# ARC.net
KiCad netlist of a schematic drawn in Altium Designer
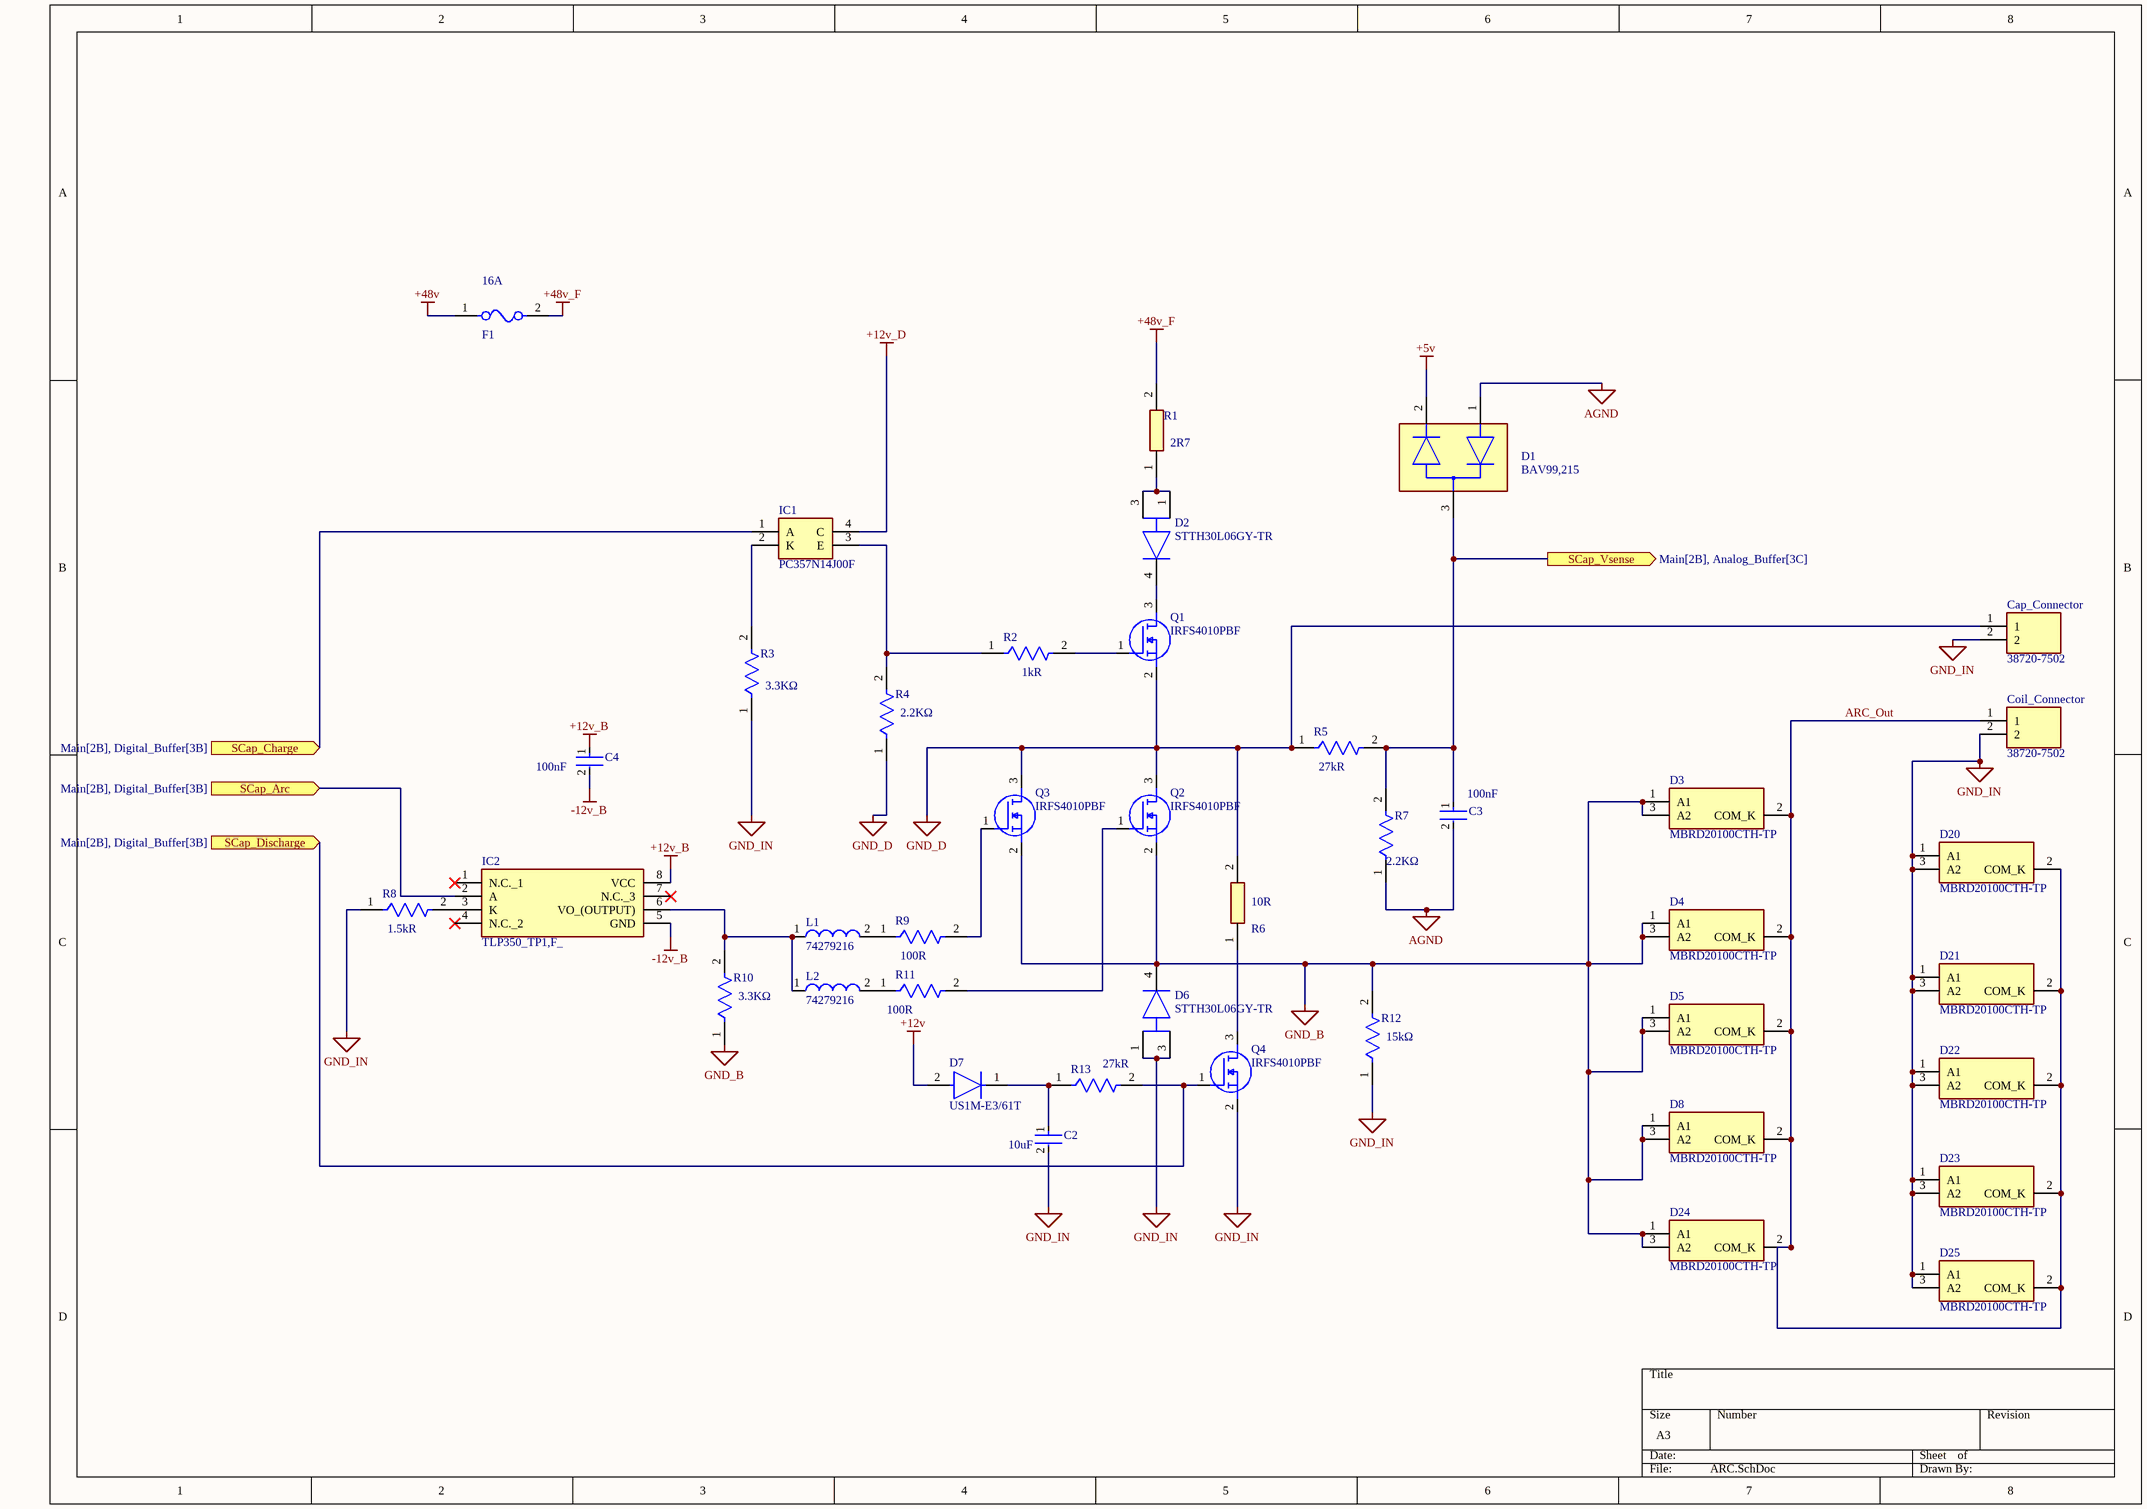
[diagram p0: ARC.SchDoc]

(export (version "E")
  (design (tool "Eeschema 10.0.6"))
  (components
    (comp (ref "C2")
      (value "GRM31CR71E106KA12L")
      (footprint "FP-GRM31C-0_2-e0_3_0_8-MFG")
      (description "Chip Multilayer Ceramic Capacitors for General Purpose, 1206, 10uF, X7R, 15%, 10%, 25V")
      (fields
        (field (name "TOLERANCE") "10%")
        (field (name "VOLTAGE") "25V")
        (field (name "CAPACITANCE") "10uF")
      )
      (libsource (lib "Altium Content Vault") (part "02cd4be3c70576c341d710602a673aa"))
    )
    (comp (ref "C3")
      (value "12065C104KAT2A")
      (footprint "FP-1206-L_3_2_0_2-W_1_6_0-MFG")
      (description "General Purpose Ceramic Capacitor, 1206, 100nF, 10%, X7R, 15%, 50V")
      (fields
        (field (name "TOLERANCE") "10%")
        (field (name "VOLTAGE") "50V")
        (field (name "CAPACITANCE") "100nF")
      )
      (libsource (lib "Altium Content Vault") (part "02cd4be3c70576c341d710602a673aa"))
    )
    (comp (ref "C4")
      (value "12065C104KAT2A")
      (footprint "FP-1206-L_3_2_0_2-W_1_6_0-MFG")
      (description "General Purpose Ceramic Capacitor, 1206, 100nF, 10%, X7R, 15%, 50V")
      (fields
        (field (name "TOLERANCE") "10%")
        (field (name "VOLTAGE") "50V")
        (field (name "CAPACITANCE") "100nF")
      )
      (libsource (lib "Altium Content Vault") (part "02cd4be3c70576c341d710602a673aa"))
    )
    (comp (ref "Cap_Connector")
      (value "38720-7502")
      (footprint "SamacSys:387207502")
      (description "Connector")
      (fields (field (name "MOUSER PART NUMBER") "538-38720-7502"))
      (libsource (lib "*") (part "38720-7502"))
    )
    (comp (ref "Coil_Connector")
      (value "38720-7502")
      (footprint "SamacSys:387207502")
      (description "Connector")
      (fields (field (name "MOUSER PART NUMBER") "538-38720-7502"))
      (libsource (lib "*") (part "38720-7502"))
    )
    (comp (ref "D1")
      (value "BAV99,215")
      (footprint "FP-SOT23-MFG")
      (description "DIODE ARRAY GP 100V 215MA SOT23")
      (libsource (lib "Altium Content Vault") (part "86a7eb6839269cc1691df5cbdd99f75"))
    )
    (comp (ref "D2")
      (value "STTH30L06GY-TR")
      (footprint "FP-D2PAK-MFG")
      (description "DIODE GEN PURP 600V 30A D2PAK")
      (fields
        (field (name "OCTOPART") "https://octopart.com/stth30l06gy-tr-stmicroelectronics-26451410")
        (field (name "MANUFACTURER") "STMicroelectronics")
      )
      (libsource (lib "Altium Content Vault") (part "255d24a1d5026c405cb8a6d03432c93"))
    )
    (comp (ref "D3")
      (value "MBRD20100CTH-TP")
      (footprint "SamacSys:MBRD20100CTHTP")
      (description "Schottky Diode")
      (fields (field (name "MOUSER PART NUMBER") "833-MBRD20100CTH-TP"))
      (libsource (lib "*") (part "MBRD20100CTH-TP"))
    )
    (comp (ref "D4")
      (value "MBRD20100CTH-TP")
      (footprint "SamacSys:MBRD20100CTHTP")
      (description "Schottky Diode")
      (fields (field (name "MOUSER PART NUMBER") "833-MBRD20100CTH-TP"))
      (libsource (lib "*") (part "MBRD20100CTH-TP"))
    )
    (comp (ref "D5")
      (value "MBRD20100CTH-TP")
      (footprint "SamacSys:MBRD20100CTHTP")
      (description "Schottky Diode")
      (fields (field (name "MOUSER PART NUMBER") "833-MBRD20100CTH-TP"))
      (libsource (lib "*") (part "MBRD20100CTH-TP"))
    )
    (comp (ref "D6")
      (value "STTH30L06GY-TR")
      (footprint "FP-D2PAK-MFG")
      (description "DIODE GEN PURP 600V 30A D2PAK")
      (fields
        (field (name "OCTOPART") "https://octopart.com/stth30l06gy-tr-stmicroelectronics-26451410")
        (field (name "MANUFACTURER") "STMicroelectronics")
      )
      (libsource (lib "Altium Content Vault") (part "255d24a1d5026c405cb8a6d03432c93"))
    )
    (comp (ref "D7")
      (value "US1M-E3/61T")
      (footprint "FP-95400-MFG")
      (description "DIODE GEN PURP 1KV 1A DO214AC")
      (fields
        (field (name "OCTOPART") "https://octopart.com/us1m-e3%2F61t-vishay-39553152")
        (field (name "MANUFACTURER") "Vishay")
      )
      (libsource (lib "Altium Content Vault") (part "d7152d700b627762746794eb795d46e"))
    )
    (comp (ref "D8")
      (value "MBRD20100CTH-TP")
      (footprint "SamacSys:MBRD20100CTHTP")
      (description "Schottky Diode")
      (fields (field (name "MOUSER PART NUMBER") "833-MBRD20100CTH-TP"))
      (libsource (lib "*") (part "MBRD20100CTH-TP"))
    )
    (comp (ref "D20")
      (value "MBRD20100CTH-TP")
      (footprint "SamacSys:MBRD20100CTHTP")
      (description "Schottky Diode")
      (fields (field (name "MOUSER PART NUMBER") "833-MBRD20100CTH-TP"))
      (libsource (lib "*") (part "MBRD20100CTH-TP"))
    )
    (comp (ref "D21")
      (value "MBRD20100CTH-TP")
      (footprint "SamacSys:MBRD20100CTHTP")
      (description "Schottky Diode")
      (fields (field (name "MOUSER PART NUMBER") "833-MBRD20100CTH-TP"))
      (libsource (lib "*") (part "MBRD20100CTH-TP"))
    )
    (comp (ref "D22")
      (value "MBRD20100CTH-TP")
      (footprint "SamacSys:MBRD20100CTHTP")
      (description "Schottky Diode")
      (fields (field (name "MOUSER PART NUMBER") "833-MBRD20100CTH-TP"))
      (libsource (lib "*") (part "MBRD20100CTH-TP"))
    )
    (comp (ref "D23")
      (value "MBRD20100CTH-TP")
      (footprint "SamacSys:MBRD20100CTHTP")
      (description "Schottky Diode")
      (fields (field (name "MOUSER PART NUMBER") "833-MBRD20100CTH-TP"))
      (libsource (lib "*") (part "MBRD20100CTH-TP"))
    )
    (comp (ref "D24")
      (value "MBRD20100CTH-TP")
      (footprint "SamacSys:MBRD20100CTHTP")
      (description "Schottky Diode")
      (fields (field (name "MOUSER PART NUMBER") "833-MBRD20100CTH-TP"))
      (libsource (lib "*") (part "MBRD20100CTH-TP"))
    )
    (comp (ref "D25")
      (value "MBRD20100CTH-TP")
      (footprint "SamacSys:MBRD20100CTHTP")
      (description "Schottky Diode")
      (fields (field (name "MOUSER PART NUMBER") "833-MBRD20100CTH-TP"))
      (libsource (lib "*") (part "MBRD20100CTH-TP"))
    )
    (comp (ref "F1")
      (value "0031.8231")
      (footprint "FP-0031_8231-MFG")
      (description "FUSE BLOK CARTRIDGE 600V 16A PCB")
      (fields
        (field (name "OCTOPART") "https://octopart.com/0031.8231-schurter-8659")
        (field (name "FUSE CURRENT") "16A")
        (field (name "MANUFACTURER") "Schurter")
      )
      (libsource (lib "Altium Content Vault") (part "5bcf9b9f640e542cf0359d10258e979"))
    )
    (comp (ref "IC1")
      (value "PC357N14J00F")
      (footprint "SamacSys:SOP254P675X300-4N")
      (description "Integrated Circuit")
      (libsource (lib "*") (part "PC357N14J00F"))
    )
    (comp (ref "IC2")
      (value "TLP350_TP1,F_")
      (footprint "SamacSys:DIP762W60P254L966H485Q8N")
      (description "Integrated Circuit")
      (fields
        (field (name "MANUFACTURER_PART_NUMBER") "TLP350(TP1,F)")
        (field (name "MOUSER PART NUMBER") "757-TLP350(TP1,F)")
      )
      (libsource (lib "*") (part "TLP350_TP1,F_"))
    )
    (comp (ref "L1")
      (value "74279216")
      (footprint "SMD-1206")
      (description "SMD EMI Suppression Ferrite Bead WE-CBF, Z = 1200 Ohm")
      (libsource (lib "Altium Content Vault") (part "PAS-IND-INDUCTOR-2"))
    )
    (comp (ref "L2")
      (value "74279216")
      (footprint "SMD-1206")
      (description "SMD EMI Suppression Ferrite Bead WE-CBF, Z = 1200 Ohm")
      (libsource (lib "Altium Content Vault") (part "PAS-IND-INDUCTOR-2"))
    )
    (comp (ref "Q1")
      (value "IRFS4010PBF")
      (footprint "SamacSys:IDB30E60")
      (description "MOSFET (N-Channel)")
      (fields (field (name "MOUSER PART NUMBER") "942-IRFS4010PBF"))
      (libsource (lib "*") (part "IRFS4010PBF"))
    )
    (comp (ref "Q2")
      (value "IRFS4010PBF")
      (footprint "SamacSys:IDB30E60")
      (description "MOSFET (N-Channel)")
      (fields (field (name "MOUSER PART NUMBER") "942-IRFS4010PBF"))
      (libsource (lib "*") (part "IRFS4010PBF"))
    )
    (comp (ref "Q3")
      (value "IRFS4010PBF")
      (footprint "SamacSys:IDB30E60")
      (description "MOSFET (N-Channel)")
      (fields (field (name "MOUSER PART NUMBER") "942-IRFS4010PBF"))
      (libsource (lib "*") (part "IRFS4010PBF"))
    )
    (comp (ref "Q4")
      (value "IRFS4010PBF")
      (footprint "SamacSys:IDB30E60")
      (description "MOSFET (N-Channel)")
      (fields (field (name "MOUSER PART NUMBER") "942-IRFS4010PBF"))
      (libsource (lib "*") (part "IRFS4010PBF"))
    )
    (comp (ref "R1")
      (value "2R7")
      (footprint "SamacSys:CP001027K00JE663")
      (description "Resistor")
      (fields
        (field (name "MANUFACTURER_PART_NUMBER") "CP001010R00JE66")
        (field (name "MOUSER PART NUMBER") "71-CP001010R00JE66")
      )
      (libsource (lib "*") (part "CP001010R00JE66"))
    )
    (comp (ref "R2")
      (value "CR1206-FX-1001ELF")
      (footprint "FP-CR1206-IPC_A")
      (description "Thick Film Chip Resistors 1206 1kΩ 0.25W 1% 100ppm/°C")
      (fields (field (name "TOLERANCE") "1%") (field (name "RESISTANCE") "1kR"))
      (libsource (lib "Altium Content Vault") (part "1029c3af85768c4190bb7ad29bc67b5"))
    )
    (comp (ref "R3")
      (value "3.3KΩ")
      (footprint "FP-CRGCQ1206-IPC_C")
      (description "CRGCQ1206 3.3KΩ 0.25W 5% ±100ppm/°C 200V")
      (fields
        (field (name "OCTOPART") "https://octopart.com/crgcq1206j3k3-te+connectivity-91018329")
        (field (name "MANUFACTURER PART NUMBER") "CRGCQ1206J3K3")
      )
      (libsource (lib "Altium Content Vault") (part "1029c3af85768c4190bb7ad29bc67b5"))
    )
    (comp (ref "R4")
      (value "2.2KΩ")
      (footprint "FP-CRGCQ1206-IPC_C")
      (description "CRGCQ 1206 2K2 5%")
      (fields (field (name "TOLERANCE") "0.05") (field (name "MANUFACTURER PART NUMBER") "CRGCQ1206J2K2"))
      (libsource (lib "Altium Content Vault") (part "1029c3af85768c4190bb7ad29bc67b5"))
    )
    (comp (ref "R5")
      (value "RC3216J273CS")
      (footprint "FP-RC3216-IPC_A")
      (description "Res Thick Film 1206 27kΩ 5% 0.25W ±100ppm/°C Molded SMD T/R")
      (fields (field (name "TOLERANCE") "5%") (field (name "RESISTANCE") "27kR"))
      (libsource (lib "Altium Content Vault") (part "1029c3af85768c4190bb7ad29bc67b5"))
    )
    (comp (ref "R6")
      (value "10R")
      (footprint "SamacSys:CP001027K00JE663")
      (description "Resistor")
      (fields
        (field (name "MANUFACTURER_PART_NUMBER") "CP001010R00JE66")
        (field (name "MOUSER PART NUMBER") "71-CP001010R00JE66")
      )
      (libsource (lib "*") (part "CP001010R00JE66"))
    )
    (comp (ref "R7")
      (value "2.2KΩ")
      (footprint "FP-CRGCQ1206-IPC_C")
      (description "CRGCQ 1206 2K2 5%")
      (fields (field (name "TOLERANCE") "0.05") (field (name "MANUFACTURER PART NUMBER") "CRGCQ1206J2K2"))
      (libsource (lib "Altium Content Vault") (part "1029c3af85768c4190bb7ad29bc67b5"))
    )
    (comp (ref "R8")
      (value "CRCW12061K50FKEA")
      (footprint "FP-CRCW1206-e3-IPC_C")
      (description "RES Thick Film, 1.5kΩ, 1%, 0.25W, 100ppm/°C, 1206")
      (fields (field (name "TOLERANCE") "1%") (field (name "RESISTANCE") "1.5kR"))
      (libsource (lib "Altium Content Vault") (part "1029c3af85768c4190bb7ad29bc67b5"))
    )
    (comp (ref "R9")
      (value "CRCW1206100RFKEA")
      (footprint "FP-CRCW1206-e3-MFG")
      (description "RES Thick Film, 100Ω, 1%, 0.25W, 100ppm/°C, 1206")
      (fields (field (name "RESISTANCE") "100R") (field (name "TOLERANCE") "1%"))
      (libsource (lib "Altium Content Vault") (part "1029c3af85768c4190bb7ad29bc67b5"))
    )
    (comp (ref "R10")
      (value "CRGCQ1206F3K3")
      (footprint "FP-CRGCQ1206-IPC_C")
      (description "CRGCQ1206 3.3KΩ 0.25W 1% ±100ppm/°C 200V")
      (fields
        (field (name "TOLERANCE") "0.01")
        (field (name "RESISTANCE") "3.3KΩ")
        (field (name "MANUFACTURER") "TE Connectivity")
      )
      (libsource (lib "Altium Content Vault") (part "1029c3af85768c4190bb7ad29bc67b5"))
    )
    (comp (ref "R11")
      (value "CRCW1206100RFKEA")
      (footprint "FP-CRCW1206-e3-MFG")
      (description "RES Thick Film, 100Ω, 1%, 0.25W, 100ppm/°C, 1206")
      (fields (field (name "RESISTANCE") "100R") (field (name "TOLERANCE") "1%"))
      (libsource (lib "Altium Content Vault") (part "1029c3af85768c4190bb7ad29bc67b5"))
    )
    (comp (ref "R12")
      (value "ERJ-8ENF1502V")
      (footprint "FP-ERJ8EN-MFG")
      (fields (field (name "RESISTANCE") "15kΩ") (field (name "TOLERANCE") "1%"))
      (libsource (lib "Altium Content Vault") (part "1029c3af85768c4190bb7ad29bc67b5"))
    )
    (comp (ref "R13")
      (value "RC3216J273CS")
      (footprint "FP-RC3216-IPC_A")
      (description "Res Thick Film 1206 27kΩ 5% 0.25W ±100ppm/°C Molded SMD T/R")
      (fields (field (name "TOLERANCE") "5%") (field (name "RESISTANCE") "27kR"))
      (libsource (lib "Altium Content Vault") (part "1029c3af85768c4190bb7ad29bc67b5"))
    )
  )
  (nets
    (net (code "1") (name "+5v") (class "Default")
      (node (ref "D1") (pin "2") (pinfunction "2_2") (pintype "passive"))
    )
    (net (code "2") (name "+12v") (class "Default")
      (node (ref "D7") (pin "2") (pinfunction "A_2") (pintype "passive"))
    )
    (net (code "3") (name "+12v_B") (class "Default")
      (node (ref "C4") (pin "1") (pinfunction "1_1") (pintype "passive"))
      (node (ref "IC2") (pin "8") (pinfunction "VCC_8") (pintype "passive"))
    )
    (net (code "4") (name "+12v_D") (class "Default")
      (node (ref "IC1") (pin "4") (pinfunction "C_4") (pintype "passive"))
    )
    (net (code "5") (name "+48v") (class "Default")
      (node (ref "F1") (pin "1") (pinfunction "1_1") (pintype "passive"))
    )
    (net (code "6") (name "+48v_F") (class "Default")
      (node (ref "F1") (pin "2") (pinfunction "2_2") (pintype "passive"))
      (node (ref "R1") (pin "2") (pinfunction "2_2") (pintype "passive"))
    )
    (net (code "7") (name "-12v_B") (class "Default")
      (node (ref "C4") (pin "2") (pinfunction "2_2") (pintype "passive"))
      (node (ref "IC2") (pin "5") (pinfunction "GND_5") (pintype "passive"))
    )
    (net (code "8") (name "/ARC_Out") (class "Default")
      (node (ref "Coil_Connector") (pin "1") (pinfunction "1_1") (pintype "passive"))
      (node (ref "D20") (pin "2") (pinfunction "COM_K_2") (pintype "passive"))
      (node (ref "D21") (pin "2") (pinfunction "COM_K_2") (pintype "passive"))
      (node (ref "D22") (pin "2") (pinfunction "COM_K_2") (pintype "passive"))
      (node (ref "D23") (pin "2") (pinfunction "COM_K_2") (pintype "passive"))
      (node (ref "D24") (pin "2") (pinfunction "COM_K_2") (pintype "passive"))
      (node (ref "D25") (pin "2") (pinfunction "COM_K_2") (pintype "passive"))
      (node (ref "D3") (pin "2") (pinfunction "COM_K_2") (pintype "passive"))
      (node (ref "D4") (pin "2") (pinfunction "COM_K_2") (pintype "passive"))
      (node (ref "D5") (pin "2") (pinfunction "COM_K_2") (pintype "passive"))
      (node (ref "D8") (pin "2") (pinfunction "COM_K_2") (pintype "passive"))
    )
    (net (code "9") (name "/SCap_Arc") (class "Default")
      (node (ref "IC2") (pin "2") (pinfunction "A_2") (pintype "passive"))
    )
    (net (code "10") (name "/SCap_Charge") (class "Default")
      (node (ref "IC1") (pin "1") (pinfunction "A_1") (pintype "passive"))
    )
    (net (code "11") (name "/SCap_Discharge") (class "Default")
      (node (ref "Q4") (pin "1") (pinfunction "G_1") (pintype "passive"))
      (node (ref "R13") (pin "2") (pinfunction "2_2") (pintype "passive"))
    )
    (net (code "12") (name "/SCap_Vsense") (class "Default")
      (node (ref "C3") (pin "1") (pinfunction "1_1") (pintype "passive"))
      (node (ref "D1") (pin "3") (pinfunction "3_3") (pintype "passive"))
      (node (ref "R5") (pin "2") (pinfunction "2_2") (pintype "passive"))
      (node (ref "R7") (pin "2") (pinfunction "2_2") (pintype "passive"))
    )
    (net (code "13") (name "AGND") (class "Default")
      (node (ref "C3") (pin "2") (pinfunction "2_2") (pintype "passive"))
      (node (ref "D1") (pin "1") (pinfunction "1_1") (pintype "passive"))
      (node (ref "R7") (pin "1") (pinfunction "1_1") (pintype "passive"))
    )
    (net (code "14") (name "GND_B") (class "Default")
      (node (ref "D24") (pin "1") (pinfunction "A1_1") (pintype "passive"))
      (node (ref "D24") (pin "3") (pinfunction "A2_3") (pintype "passive"))
      (node (ref "D3") (pin "1") (pinfunction "A1_1") (pintype "passive"))
      (node (ref "D3") (pin "3") (pinfunction "A2_3") (pintype "passive"))
      (node (ref "D4") (pin "1") (pinfunction "A1_1") (pintype "passive"))
      (node (ref "D4") (pin "3") (pinfunction "A2_3") (pintype "passive"))
      (node (ref "D5") (pin "1") (pinfunction "A1_1") (pintype "passive"))
      (node (ref "D5") (pin "3") (pinfunction "A2_3") (pintype "passive"))
      (node (ref "D6") (pin "4") (pinfunction "K_4") (pintype "passive"))
      (node (ref "D8") (pin "1") (pinfunction "A1_1") (pintype "passive"))
      (node (ref "D8") (pin "3") (pinfunction "A2_3") (pintype "passive"))
      (node (ref "Q2") (pin "2") (pinfunction "S_2") (pintype "passive"))
      (node (ref "Q3") (pin "2") (pinfunction "S_2") (pintype "passive"))
      (node (ref "R10") (pin "1") (pinfunction "1_1") (pintype "passive"))
      (node (ref "R12") (pin "2") (pinfunction "2_2") (pintype "passive"))
    )
    (net (code "15") (name "GND_D") (class "Default")
      (node (ref "Cap_Connector") (pin "1") (pinfunction "1_1") (pintype "passive"))
      (node (ref "Q1") (pin "2") (pinfunction "S_2") (pintype "passive"))
      (node (ref "Q2") (pin "3") (pinfunction "D_3") (pintype "passive"))
      (node (ref "Q3") (pin "3") (pinfunction "D_3") (pintype "passive"))
      (node (ref "R4") (pin "1") (pinfunction "1_1") (pintype "passive"))
      (node (ref "R5") (pin "1") (pinfunction "1_1") (pintype "passive"))
      (node (ref "R6") (pin "2") (pinfunction "2_2") (pintype "passive"))
    )
    (net (code "16") (name "GND_IN") (class "Default")
      (node (ref "C2") (pin "2") (pinfunction "2_2") (pintype "passive"))
      (node (ref "Cap_Connector") (pin "2") (pinfunction "2_2") (pintype "passive"))
      (node (ref "Coil_Connector") (pin "2") (pinfunction "2_2") (pintype "passive"))
      (node (ref "D20") (pin "1") (pinfunction "A1_1") (pintype "passive"))
      (node (ref "D20") (pin "3") (pinfunction "A2_3") (pintype "passive"))
      (node (ref "D21") (pin "1") (pinfunction "A1_1") (pintype "passive"))
      (node (ref "D21") (pin "3") (pinfunction "A2_3") (pintype "passive"))
      (node (ref "D22") (pin "1") (pinfunction "A1_1") (pintype "passive"))
      (node (ref "D22") (pin "3") (pinfunction "A2_3") (pintype "passive"))
      (node (ref "D23") (pin "1") (pinfunction "A1_1") (pintype "passive"))
      (node (ref "D23") (pin "3") (pinfunction "A2_3") (pintype "passive"))
      (node (ref "D25") (pin "1") (pinfunction "A1_1") (pintype "passive"))
      (node (ref "D25") (pin "3") (pinfunction "A2_3") (pintype "passive"))
      (node (ref "D6") (pin "1") (pinfunction "A_1") (pintype "passive"))
      (node (ref "D6") (pin "3") (pinfunction "A_3") (pintype "passive"))
      (node (ref "Q4") (pin "2") (pinfunction "S_2") (pintype "passive"))
      (node (ref "R12") (pin "1") (pinfunction "1_1") (pintype "passive"))
      (node (ref "R3") (pin "1") (pinfunction "1_1") (pintype "passive"))
      (node (ref "R8") (pin "1") (pinfunction "1_1") (pintype "passive"))
    )
    (net (code "17") (name "Net-(D2-A-Pad1)") (class "Default")
      (node (ref "D2") (pin "1") (pinfunction "A_1") (pintype "passive"))
      (node (ref "D2") (pin "3") (pinfunction "A_3") (pintype "passive"))
      (node (ref "R1") (pin "1") (pinfunction "1_1") (pintype "passive"))
    )
    (net (code "18") (name "Net-(D2-K)") (class "Default")
      (node (ref "D2") (pin "4") (pinfunction "K_4") (pintype "passive"))
      (node (ref "Q1") (pin "3") (pinfunction "D_3") (pintype "passive"))
    )
    (net (code "19") (name "Net-(D7-C)") (class "Default")
      (node (ref "C2") (pin "1") (pinfunction "1_1") (pintype "passive"))
      (node (ref "D7") (pin "1") (pinfunction "C_1") (pintype "passive"))
      (node (ref "R13") (pin "1") (pinfunction "1_1") (pintype "passive"))
    )
    (net (code "20") (name "Net-(IC1-E)") (class "Default")
      (node (ref "IC1") (pin "3") (pinfunction "E_3") (pintype "passive"))
      (node (ref "R2") (pin "1") (pinfunction "1_1") (pintype "passive"))
      (node (ref "R4") (pin "2") (pinfunction "2_2") (pintype "passive"))
    )
    (net (code "21") (name "Net-(IC1-K)") (class "Default")
      (node (ref "IC1") (pin "2") (pinfunction "K_2") (pintype "passive"))
      (node (ref "R3") (pin "2") (pinfunction "2_2") (pintype "passive"))
    )
    (net (code "22") (name "Net-(IC2-K)") (class "Default")
      (node (ref "IC2") (pin "3") (pinfunction "K_3") (pintype "passive"))
      (node (ref "R8") (pin "2") (pinfunction "2_2") (pintype "passive"))
    )
    (net (code "23") (name "Net-(IC2-VO_(OUTPUT))") (class "Default")
      (node (ref "IC2") (pin "6") (pinfunction "VO_(OUTPUT)_6") (pintype "passive"))
      (node (ref "L1") (pin "1") (pinfunction "1_1") (pintype "passive"))
      (node (ref "L2") (pin "1") (pinfunction "1_1") (pintype "passive"))
      (node (ref "R10") (pin "2") (pinfunction "2_2") (pintype "passive"))
    )
    (net (code "24") (name "Net-(L1-Pad2)") (class "Default")
      (node (ref "L1") (pin "2") (pinfunction "2_2") (pintype "passive"))
      (node (ref "R9") (pin "1") (pinfunction "1_1") (pintype "passive"))
    )
    (net (code "25") (name "Net-(L2-Pad2)") (class "Default")
      (node (ref "L2") (pin "2") (pinfunction "2_2") (pintype "passive"))
      (node (ref "R11") (pin "1") (pinfunction "1_1") (pintype "passive"))
    )
    (net (code "26") (name "Net-(Q1-G)") (class "Default")
      (node (ref "Q1") (pin "1") (pinfunction "G_1") (pintype "passive"))
      (node (ref "R2") (pin "2") (pinfunction "2_2") (pintype "passive"))
    )
    (net (code "27") (name "Net-(Q2-G)") (class "Default")
      (node (ref "Q2") (pin "1") (pinfunction "G_1") (pintype "passive"))
      (node (ref "R11") (pin "2") (pinfunction "2_2") (pintype "passive"))
    )
    (net (code "28") (name "Net-(Q3-G)") (class "Default")
      (node (ref "Q3") (pin "1") (pinfunction "G_1") (pintype "passive"))
      (node (ref "R9") (pin "2") (pinfunction "2_2") (pintype "passive"))
    )
    (net (code "29") (name "Net-(Q4-D)") (class "Default")
      (node (ref "Q4") (pin "3") (pinfunction "D_3") (pintype "passive"))
      (node (ref "R6") (pin "1") (pinfunction "1_1") (pintype "passive"))
    )
    (net (code "30") (name "unconnected-(IC2-N.C._1-Pad1)") (class "Default")
      (node (ref "IC2") (pin "1") (pinfunction "N.C._1_1") (pintype "passive+no_connect"))
    )
    (net (code "31") (name "unconnected-(IC2-N.C._2-Pad4)") (class "Default")
      (node (ref "IC2") (pin "4") (pinfunction "N.C._2_4") (pintype "passive+no_connect"))
    )
    (net (code "32") (name "unconnected-(IC2-N.C._3-Pad7)") (class "Default")
      (node (ref "IC2") (pin "7") (pinfunction "N.C._3_7") (pintype "passive+no_connect"))
    )
  )
)
